# 101_GridPos1.net
KiCad netlist of a schematic drawn in Altium Designer
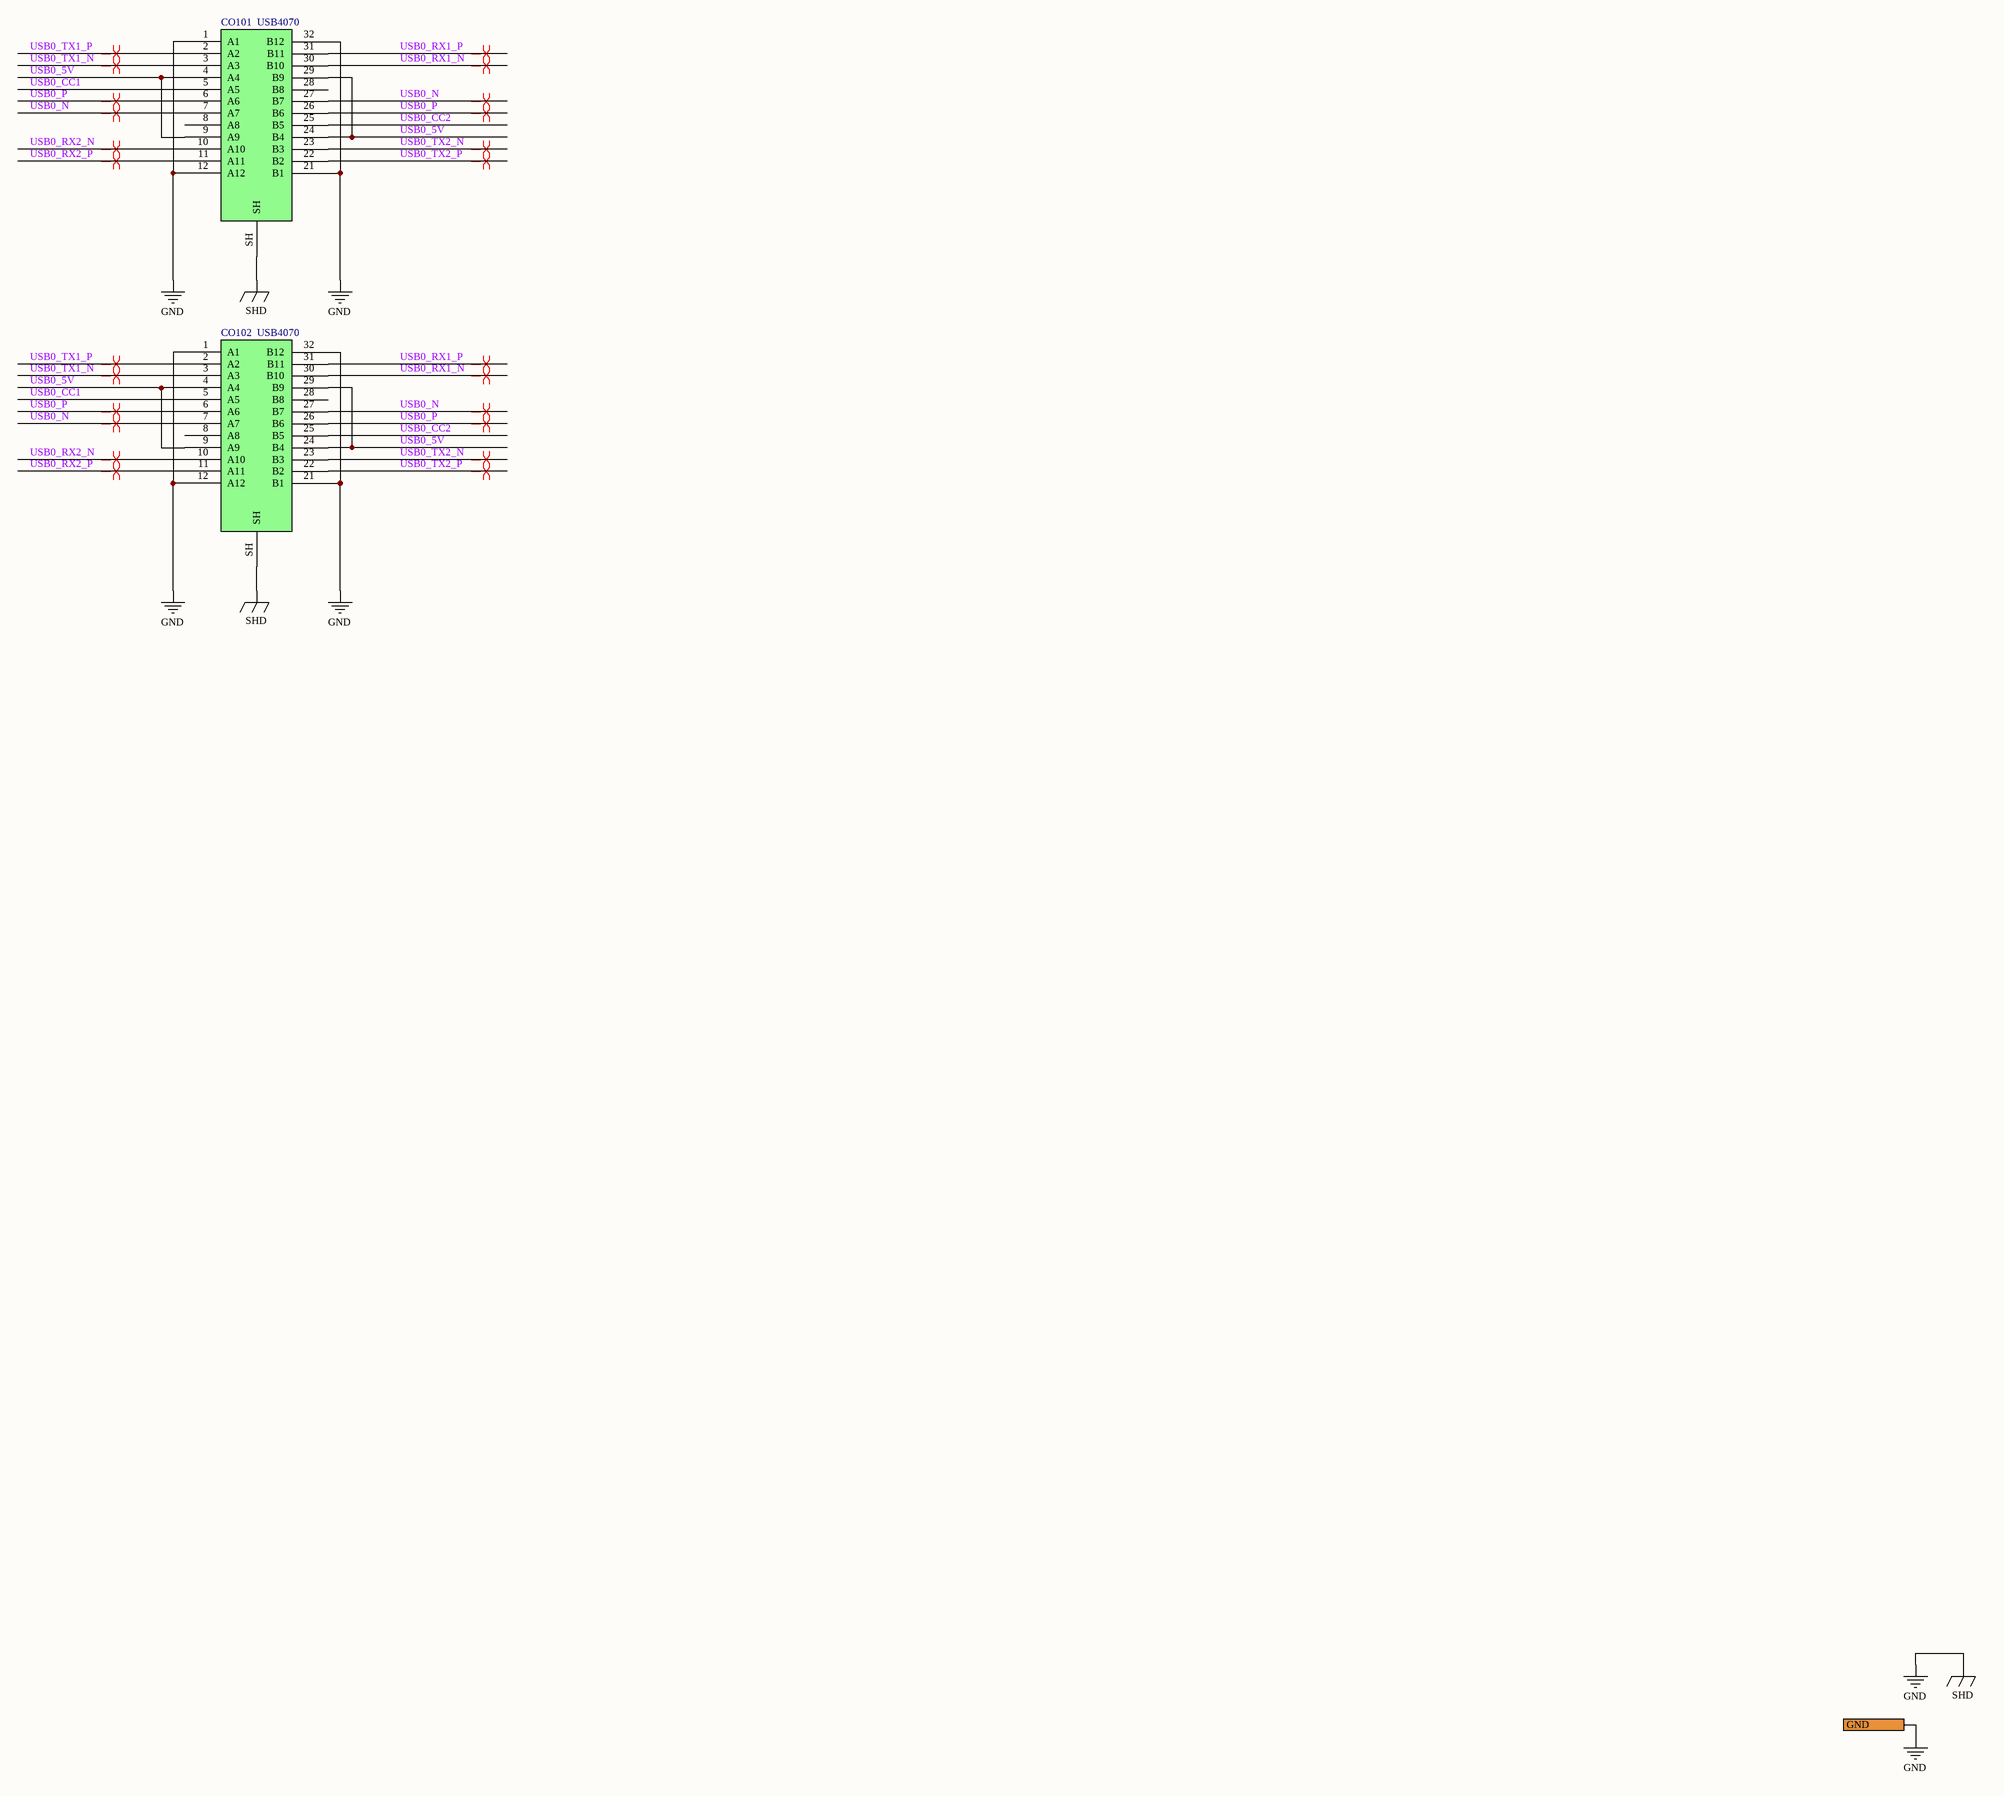
[diagram p0: 101_GridPos1.SchDoc]

(export (version "E")
  (design (tool "Eeschema 10.0.6"))
  (components
    (comp (ref "CO101")
      (value "USB4070")
      (footprint "USB4070-30-C")
      (description "USB4070-30-C")
      (fields (field (name "REFVAL") "USB4070") (field (name "PART NUMBER") "CO0021"))
      (libsource (lib "GTS_Database") (part "USB-CC"))
    )
    (comp (ref "CO102")
      (value "USB4070")
      (footprint "USB4070-30-C")
      (description "USB4070-30-C")
      (fields (field (name "REFVAL") "USB4070") (field (name "PART NUMBER") "CO0021"))
      (libsource (lib "GTS_Database") (part "USB-CC"))
    )
  )
  (nets
    (net (code "1") (name "/USB0_5V") (class "Default")
      (node (ref "CO101") (pin "24") (pinfunction "B4_24") (pintype "passive"))
      (node (ref "CO101") (pin "29") (pinfunction "B9_29") (pintype "passive"))
      (node (ref "CO101") (pin "4") (pinfunction "A4_4") (pintype "passive"))
      (node (ref "CO101") (pin "9") (pinfunction "A9_9") (pintype "passive"))
      (node (ref "CO102") (pin "24") (pinfunction "B4_24") (pintype "passive"))
      (node (ref "CO102") (pin "29") (pinfunction "B9_29") (pintype "passive"))
      (node (ref "CO102") (pin "4") (pinfunction "A4_4") (pintype "passive"))
      (node (ref "CO102") (pin "9") (pinfunction "A9_9") (pintype "passive"))
    )
    (net (code "2") (name "/USB0_CC1") (class "Default")
      (node (ref "CO101") (pin "5") (pinfunction "A5_5") (pintype "passive"))
      (node (ref "CO102") (pin "5") (pinfunction "A5_5") (pintype "passive"))
    )
    (net (code "3") (name "/USB0_CC2") (class "Default")
      (node (ref "CO101") (pin "25") (pinfunction "B5_25") (pintype "passive"))
      (node (ref "CO102") (pin "25") (pinfunction "B5_25") (pintype "passive"))
    )
    (net (code "4") (name "/USB0_N") (class "Default")
      (node (ref "CO101") (pin "27") (pinfunction "B7_27") (pintype "passive"))
      (node (ref "CO101") (pin "7") (pinfunction "A7_7") (pintype "passive"))
      (node (ref "CO102") (pin "27") (pinfunction "B7_27") (pintype "passive"))
      (node (ref "CO102") (pin "7") (pinfunction "A7_7") (pintype "passive"))
    )
    (net (code "5") (name "/USB0_P") (class "Default")
      (node (ref "CO101") (pin "26") (pinfunction "B6_26") (pintype "passive"))
      (node (ref "CO101") (pin "6") (pinfunction "A6_6") (pintype "passive"))
      (node (ref "CO102") (pin "26") (pinfunction "B6_26") (pintype "passive"))
      (node (ref "CO102") (pin "6") (pinfunction "A6_6") (pintype "passive"))
    )
    (net (code "6") (name "/USB0_RX1_N") (class "Default")
      (node (ref "CO101") (pin "30") (pinfunction "B10_30") (pintype "passive"))
      (node (ref "CO102") (pin "30") (pinfunction "B10_30") (pintype "passive"))
    )
    (net (code "7") (name "/USB0_RX1_P") (class "Default")
      (node (ref "CO101") (pin "31") (pinfunction "B11_31") (pintype "passive"))
      (node (ref "CO102") (pin "31") (pinfunction "B11_31") (pintype "passive"))
    )
    (net (code "8") (name "/USB0_RX2_N") (class "Default")
      (node (ref "CO101") (pin "10") (pinfunction "A10_10") (pintype "passive"))
      (node (ref "CO102") (pin "10") (pinfunction "A10_10") (pintype "passive"))
    )
    (net (code "9") (name "/USB0_RX2_P") (class "Default")
      (node (ref "CO101") (pin "11") (pinfunction "A11_11") (pintype "passive"))
      (node (ref "CO102") (pin "11") (pinfunction "A11_11") (pintype "passive"))
    )
    (net (code "10") (name "/USB0_TX1_N") (class "Default")
      (node (ref "CO101") (pin "3") (pinfunction "A3_3") (pintype "passive"))
      (node (ref "CO102") (pin "3") (pinfunction "A3_3") (pintype "passive"))
    )
    (net (code "11") (name "/USB0_TX1_P") (class "Default")
      (node (ref "CO101") (pin "2") (pinfunction "A2_2") (pintype "passive"))
      (node (ref "CO102") (pin "2") (pinfunction "A2_2") (pintype "passive"))
    )
    (net (code "12") (name "/USB0_TX2_N") (class "Default")
      (node (ref "CO101") (pin "23") (pinfunction "B3_23") (pintype "passive"))
      (node (ref "CO102") (pin "23") (pinfunction "B3_23") (pintype "passive"))
    )
    (net (code "13") (name "/USB0_TX2_P") (class "Default")
      (node (ref "CO101") (pin "22") (pinfunction "B2_22") (pintype "passive"))
      (node (ref "CO102") (pin "22") (pinfunction "B2_22") (pintype "passive"))
    )
    (net (code "14") (name "GND") (class "Default")
      (node (ref "CO101") (pin "1") (pinfunction "A1_1") (pintype "passive"))
      (node (ref "CO101") (pin "12") (pinfunction "A12_12") (pintype "passive"))
      (node (ref "CO101") (pin "21") (pinfunction "B1_21") (pintype "passive"))
      (node (ref "CO101") (pin "32") (pinfunction "B12_32") (pintype "passive"))
      (node (ref "CO101") (pin "SH") (pinfunction "SH_SH") (pintype "power_in"))
      (node (ref "CO102") (pin "1") (pinfunction "A1_1") (pintype "passive"))
      (node (ref "CO102") (pin "12") (pinfunction "A12_12") (pintype "passive"))
      (node (ref "CO102") (pin "21") (pinfunction "B1_21") (pintype "passive"))
      (node (ref "CO102") (pin "32") (pinfunction "B12_32") (pintype "passive"))
      (node (ref "CO102") (pin "SH") (pinfunction "SH_SH") (pintype "power_in"))
    )
    (net (code "15") (name "unconnected-(CO101-A8-Pad8)") (class "Default")
      (node (ref "CO101") (pin "8") (pinfunction "A8_8") (pintype "passive"))
    )
    (net (code "16") (name "unconnected-(CO101-B8-Pad28)") (class "Default")
      (node (ref "CO101") (pin "28") (pinfunction "B8_28") (pintype "passive"))
    )
    (net (code "17") (name "unconnected-(CO102-A8-Pad8)") (class "Default")
      (node (ref "CO102") (pin "8") (pinfunction "A8_8") (pintype "passive"))
    )
    (net (code "18") (name "unconnected-(CO102-B8-Pad28)") (class "Default")
      (node (ref "CO102") (pin "28") (pinfunction "B8_28") (pintype "passive"))
    )
  )
)
